# x2go_power_v1.net
KiCad netlist of a schematic drawn in EAGLE
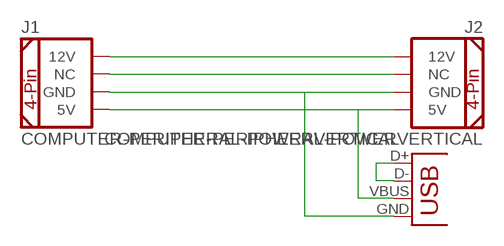
[diagram p0: schematic, sheet 1]

(export (version "E")
  (design (tool "Eeschema 10.0.6"))
  (components
    (comp (ref "J1")
      (value "COMPUTER-PERIPHERAL-POWERVERTICAL")
      (footprint "eagle-import:COMPUTER-PERIPHERAL-POWER")
      (libsource (lib "eagle-import") (part "COMPUTER-PERIPHERAL-POWERVERTICAL"))
    )
    (comp (ref "J2")
      (value "COMPUTER-PERIPHERAL-POWERVERTICAL")
      (footprint "eagle-import:COMPUTER-PERIPHERAL-POWER")
      (libsource (lib "eagle-import") (part "COMPUTER-PERIPHERAL-POWERVERTICAL"))
    )
    (comp (ref "JP1")
      (value "USB-A-S")
      (footprint "eagle-import:USB-A-S")
      (libsource (lib "eagle-import") (part "USB-A-S"))
    )
  )
  (nets
    (net (code "1") (name "Net-(J1-Pad5V)") (class "Default")
      (node (ref "J1") (pin "5V") (pinfunction "5V_5V") (pintype "passive"))
      (node (ref "J2") (pin "5V") (pinfunction "5V_5V") (pintype "passive"))
      (node (ref "JP1") (pin "VBUS") (pinfunction "VBUS_VBUS") (pintype "bidirectional"))
    )
    (net (code "2") (name "Net-(J1-Pad12V)") (class "Default")
      (node (ref "J1") (pin "12V") (pinfunction "12V_12V") (pintype "passive"))
      (node (ref "J2") (pin "12V") (pinfunction "12V_12V") (pintype "passive"))
    )
    (net (code "3") (name "Net-(J1-PadGND)") (class "Default")
      (node (ref "J1") (pin "GND") (pinfunction "GND_GND") (pintype "passive"))
      (node (ref "J2") (pin "GND") (pinfunction "GND_GND") (pintype "passive"))
      (node (ref "JP1") (pin "GND") (pinfunction "GND_GND") (pintype "bidirectional"))
    )
    (net (code "4") (name "Net-(J1-PadNC)") (class "Default")
      (node (ref "J1") (pin "NC") (pinfunction "NC_NC") (pintype "passive"))
      (node (ref "J2") (pin "NC") (pinfunction "NC_NC") (pintype "passive"))
    )
    (net (code "5") (name "Net-(JP1-PadD+)") (class "Default")
      (node (ref "JP1") (pin "D+") (pinfunction "D+_D+") (pintype "bidirectional"))
      (node (ref "JP1") (pin "D-") (pinfunction "D-_D-") (pintype "bidirectional"))
    )
  )
)
